# 4_motor.net
KiCad netlist of a schematic drawn in Altium Designer
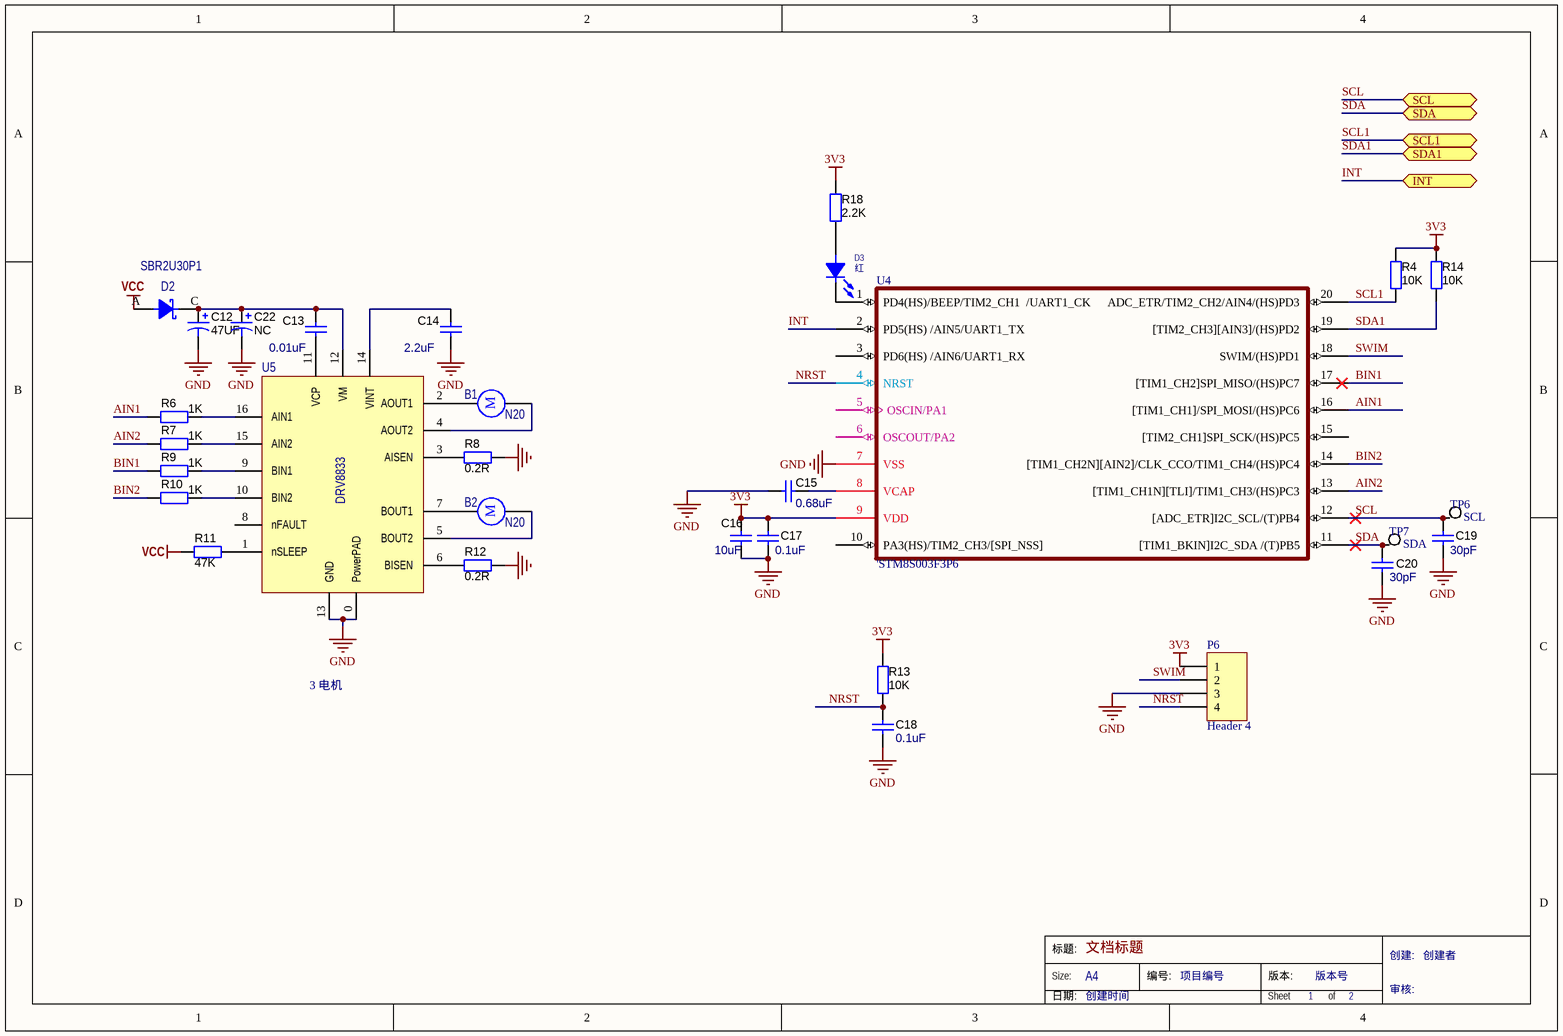
[diagram p0: 4.motor.SchDoc]

(export (version "E")
  (design (tool "Eeschema 10.0.6"))
  (components
    (comp (ref "B1")
      (value "N20")
      (footprint "2PIN/2.54MM座子")
      (description "Motor, General Kind")
      (fields (field (name "PUBLISHER") "Altium Limited"))
      (libsource (lib "Miscellaneous Devices") (part "Motor"))
    )
    (comp (ref "B2")
      (value "N20")
      (footprint "2PIN/2.54MM座子")
      (description "Motor, General Kind")
      (fields (field (name "PUBLISHER") "Altium Limited"))
      (libsource (lib "Miscellaneous Devices") (part "Motor"))
    )
    (comp (ref "C12")
      (value "47UF")
      (footprint "1206")
      (description "CAP ALUM 22UF 10V 20% SMD")
      (fields
        (field (name "PARTNUMBER") "EEE-1AA220WR")
        (field (name "MANUFACTURER") "Panasonic - ECG")
        (field (name "PUBLISHER") "National Semiconductor")
      )
      (libsource (lib "03.常用器件") (part "CAP3_pol"))
    )
    (comp (ref "C13")
      (value "0.01uF")
      (footprint "0402")
      (description "CAP, CERM, 0.01uF, 100V, +/-5%, X7R, 0603")
      (fields (field (name "PARTNUMBER") "06031C103JAT2A") (field (name "MANUFACTURER") "AVX"))
      (libsource (lib "03.常用器件") (part "CAP1_npol"))
    )
    (comp (ref "C14")
      (value "2.2uF")
      (footprint "0402")
      (description "CAP, CERM, 0.01uF, 100V, +/-5%, X7R, 0603")
      (fields (field (name "PARTNUMBER") "06031C103JAT2A") (field (name "MANUFACTURER") "AVX"))
      (libsource (lib "03.常用器件") (part "CAP1_npol"))
    )
    (comp (ref "C15")
      (value "0.68uF")
      (footprint "0402")
      (description "CAP, CERM, 0.01uF, 100V, +/-5%, X7R, 0603")
      (fields (field (name "PARTNUMBER") "06031C103JAT2A") (field (name "MANUFACTURER") "AVX"))
      (libsource (lib "03.常用器件") (part "CAP1_npol"))
    )
    (comp (ref "C16")
      (value "10uF")
      (footprint "0603")
      (description "CAP, CERM, 0.01uF, 100V, +/-5%, X7R, 0603")
      (fields (field (name "PARTNUMBER") "06031C103JAT2A") (field (name "MANUFACTURER") "AVX"))
      (libsource (lib "03.常用器件") (part "CAP1_npol"))
    )
    (comp (ref "C17")
      (value "0.1uF")
      (footprint "0402")
      (description "CAP, CERM, 0.01uF, 100V, +/-5%, X7R, 0603")
      (fields (field (name "PARTNUMBER") "06031C103JAT2A") (field (name "MANUFACTURER") "AVX"))
      (libsource (lib "03.常用器件") (part "CAP1_npol"))
    )
    (comp (ref "C18")
      (value "0.1uF")
      (footprint "0402")
      (description "CAP, CERM, 0.01uF, 100V, +/-5%, X7R, 0603")
      (fields (field (name "PARTNUMBER") "06031C103JAT2A") (field (name "MANUFACTURER") "AVX"))
      (libsource (lib "03.常用器件") (part "CAP1_npol"))
    )
    (comp (ref "C19")
      (value "30pF")
      (footprint "0402")
      (description "CAP, CERM, 0.01uF, 100V, +/-5%, X7R, 0603")
      (fields (field (name "PARTNUMBER") "06031C103JAT2A") (field (name "MANUFACTURER") "AVX"))
      (libsource (lib "03.常用器件") (part "CAP1_npol"))
    )
    (comp (ref "C20")
      (value "30pF")
      (footprint "0402")
      (description "CAP, CERM, 0.01uF, 100V, +/-5%, X7R, 0603")
      (fields (field (name "PARTNUMBER") "06031C103JAT2A") (field (name "MANUFACTURER") "AVX"))
      (libsource (lib "03.常用器件") (part "CAP1_npol"))
    )
    (comp (ref "C22")
      (value "NC")
      (footprint "1206")
      (description "CAP ALUM 22UF 10V 20% SMD")
      (fields
        (field (name "PARTNUMBER") "EEE-1AA220WR")
        (field (name "MANUFACTURER") "Panasonic - ECG")
        (field (name "PUBLISHER") "National Semiconductor")
      )
      (libsource (lib "03.常用器件") (part "CAP3_pol"))
    )
    (comp (ref "D2")
      (value "SBR2U30P1")
      (footprint "POWERDI123")
      (fields (field (name "PARTNUMBER") "?") (field (name "PUBLISHER") "Altium Limited"))
      (libsource (lib "03.常用器件") (part "Diode_Schottky"))
    )
    (comp (ref "D3")
      (value "红")
      (footprint "0603LED")
      (fields (field (name "MANUFACTURER") "?"))
      (libsource (lib "03.常用器件") (part "LED1"))
    )
    (comp (ref "P6")
      (value "Header 4")
      (footprint "排针2.54MM/4PIN")
      (description "Header, 4-Pin")
      (fields (field (name "PUBLISHER") "Altium Limited"))
      (libsource (lib "Miscellaneous Connectors") (part "Header 4"))
    )
    (comp (ref "R4")
      (value "10K")
      (footprint "0402")
      (description "RES, 1.0k ohm, 5%, 0.1W, 0603")
      (fields
        (field (name "PARTNUMBER") "RC0603JR-071KL")
        (field (name "MANUFACTURER") "Yageo America")
        (field (name "PUBLISHER") "Texas Instruments")
      )
      (libsource (lib "03.常用器件") (part "RES1"))
    )
    (comp (ref "R6")
      (value "1K")
      (footprint "0402")
      (description "RES, 1.0k ohm, 5%, 0.1W, 0603")
      (fields
        (field (name "PARTNUMBER") "RC0603JR-071KL")
        (field (name "MANUFACTURER") "Yageo America")
        (field (name "PUBLISHER") "Texas Instruments")
      )
      (libsource (lib "") (part "RES1_1"))
    )
    (comp (ref "R7")
      (value "1K")
      (footprint "0402")
      (description "RES, 1.0k ohm, 5%, 0.1W, 0603")
      (fields
        (field (name "PARTNUMBER") "RC0603JR-071KL")
        (field (name "MANUFACTURER") "Yageo America")
        (field (name "PUBLISHER") "Texas Instruments")
      )
      (libsource (lib "") (part "RES1_1"))
    )
    (comp (ref "R8")
      (value "0.2R")
      (footprint "0603")
      (description "RES, 1.0k ohm, 5%, 0.1W, 0603")
      (fields
        (field (name "PARTNUMBER") "RC0603JR-071KL")
        (field (name "MANUFACTURER") "Yageo America")
        (field (name "PUBLISHER") "Texas Instruments")
      )
      (libsource (lib "") (part "RES1_1"))
    )
    (comp (ref "R9")
      (value "1K")
      (footprint "0402")
      (description "RES, 1.0k ohm, 5%, 0.1W, 0603")
      (fields
        (field (name "PARTNUMBER") "RC0603JR-071KL")
        (field (name "MANUFACTURER") "Yageo America")
        (field (name "PUBLISHER") "Texas Instruments")
      )
      (libsource (lib "") (part "RES1_1"))
    )
    (comp (ref "R10")
      (value "1K")
      (footprint "0402")
      (description "RES, 1.0k ohm, 5%, 0.1W, 0603")
      (fields
        (field (name "PARTNUMBER") "RC0603JR-071KL")
        (field (name "MANUFACTURER") "Yageo America")
        (field (name "PUBLISHER") "Texas Instruments")
      )
      (libsource (lib "") (part "RES1_1"))
    )
    (comp (ref "R11")
      (value "47K")
      (footprint "0402")
      (description "RES, 1.0k ohm, 5%, 0.1W, 0603")
      (fields
        (field (name "PARTNUMBER") "RC0603JR-071KL")
        (field (name "MANUFACTURER") "Yageo America")
        (field (name "PUBLISHER") "Texas Instruments")
      )
      (libsource (lib "") (part "RES1_1"))
    )
    (comp (ref "R12")
      (value "0.2R")
      (footprint "0603")
      (description "RES, 1.0k ohm, 5%, 0.1W, 0603")
      (fields
        (field (name "PARTNUMBER") "RC0603JR-071KL")
        (field (name "MANUFACTURER") "Yageo America")
        (field (name "PUBLISHER") "Texas Instruments")
      )
      (libsource (lib "") (part "RES1_1"))
    )
    (comp (ref "R13")
      (value "10K")
      (footprint "0402")
      (description "RES, 1.0k ohm, 5%, 0.1W, 0603")
      (fields
        (field (name "PARTNUMBER") "RC0603JR-071KL")
        (field (name "MANUFACTURER") "Yageo America")
        (field (name "PUBLISHER") "Texas Instruments")
      )
      (libsource (lib "") (part "RES1_2"))
    )
    (comp (ref "R14")
      (value "10K")
      (footprint "0402")
      (description "RES, 1.0k ohm, 5%, 0.1W, 0603")
      (fields
        (field (name "PARTNUMBER") "RC0603JR-071KL")
        (field (name "MANUFACTURER") "Yageo America")
        (field (name "PUBLISHER") "Texas Instruments")
      )
      (libsource (lib "03.常用器件") (part "RES1"))
    )
    (comp (ref "R18")
      (value "2.2K")
      (footprint "0402")
      (description "RES, 1.0k ohm, 5%, 0.1W, 0603")
      (fields
        (field (name "PARTNUMBER") "RC0603JR-071KL")
        (field (name "MANUFACTURER") "Yageo America")
        (field (name "PUBLISHER") "Texas Instruments")
      )
      (libsource (lib "") (part "RES1_2"))
    )
    (comp (ref "TP6")
      (value "SCL")
      (footprint "测试点")
      (description "Test Point")
      (libsource (lib "my_Schlib") (part "TP"))
    )
    (comp (ref "TP7")
      (value "SDA")
      (footprint "测试点")
      (description "Test Point")
      (libsource (lib "my_Schlib") (part "TP"))
    )
    (comp (ref "U4")
      (value "'STM8S003F3P6")
      (footprint "UFQFPN20")
      (description "ST 8-bit  Microcontroller")
      (libsource (lib "Microcontroller Unit") (part "STM8S103F2P6"))
    )
    (comp (ref "U5")
      (value "DRV8833")
      (footprint "HTSSOP -16(PWP)")
      (description "DUAL H-BRIDGE MOTOR DRIVER")
      (libsource (lib "DRV8833") (part "DRV8833PWP"))
    )
  )
  (nets
    (net (code "1") (name "/AIN1") (class "Default")
      (node (ref "R6") (pin "1") (pinfunction "1_1") (pintype "passive"))
      (node (ref "U4") (pin "16") (pinfunction "[TIM1_CH1]/SPI_MOSI/(HS)PC6_16") (pintype "bidirectional"))
    )
    (net (code "2") (name "/AIN2") (class "Default")
      (node (ref "R7") (pin "1") (pinfunction "1_1") (pintype "passive"))
      (node (ref "U4") (pin "13") (pinfunction "[TIM1_CH1N][TLI]/TIM1_CH3/(HS)PC3_13") (pintype "bidirectional"))
    )
    (net (code "3") (name "/BIN1") (class "Default")
      (node (ref "R9") (pin "1") (pinfunction "1_1") (pintype "passive"))
      (node (ref "U4") (pin "17") (pinfunction "[TIM1_CH2]SPI_MISO/(HS)PC7_17") (pintype "bidirectional"))
    )
    (net (code "4") (name "/BIN2") (class "Default")
      (node (ref "R10") (pin "1") (pinfunction "1_1") (pintype "passive"))
      (node (ref "U4") (pin "14") (pinfunction "[TIM1_CH2N][AIN2]/CLK_CCO/TIM1_CH4/(HS)PC4_14") (pintype "bidirectional"))
    )
    (net (code "5") (name "/INT") (class "Default")
      (node (ref "U4") (pin "2") (pinfunction "PD5(HS)_/AIN5/UART1_TX_2") (pintype "bidirectional"))
    )
    (net (code "6") (name "/NRST") (class "Default")
      (node (ref "C18") (pin "2") (pinfunction "2_2") (pintype "passive"))
      (node (ref "P6") (pin "4") (pinfunction "4_4") (pintype "passive"))
      (node (ref "R13") (pin "2") (pinfunction "2_2") (pintype "passive"))
      (node (ref "U4") (pin "4") (pinfunction "NRST_4") (pintype "bidirectional"))
    )
    (net (code "8") (name "/SCL") (class "Default")
      (node (ref "C19") (pin "2") (pinfunction "2_2") (pintype "passive"))
      (node (ref "TP6") (pin "1") (pinfunction "1_1") (pintype "passive"))
      (node (ref "U4") (pin "12") (pinfunction "[ADC_ETR]I2C_SCL/(T)PB4_12") (pintype "bidirectional"))
    )
    (net (code "10") (name "/SCL1") (class "Default")
      (node (ref "R4") (pin "1") (pinfunction "1_1") (pintype "passive"))
      (node (ref "U4") (pin "20") (pinfunction "ADC_ETR/TIM2_CH2/AIN4/(HS)PD3_20") (pintype "bidirectional"))
    )
    (net (code "11") (name "/SDA") (class "Default")
      (node (ref "C20") (pin "2") (pinfunction "2_2") (pintype "passive"))
      (node (ref "TP7") (pin "1") (pinfunction "1_1") (pintype "passive"))
      (node (ref "U4") (pin "11") (pinfunction "[TIM1_BKIN]I2C_SDA_/(T)PB5_11") (pintype "bidirectional"))
    )
    (net (code "12") (name "/SDA1") (class "Default")
      (node (ref "R14") (pin "1") (pinfunction "1_1") (pintype "passive"))
      (node (ref "U4") (pin "19") (pinfunction "[TIM2_CH3][AIN3]/(HS)PD2_19") (pintype "bidirectional"))
    )
    (net (code "13") (name "/SWIM") (class "Default")
      (node (ref "P6") (pin "2") (pinfunction "2_2") (pintype "passive"))
      (node (ref "U4") (pin "18") (pinfunction "SWIM/(HS)PD1_18") (pintype "bidirectional"))
    )
    (net (code "14") (name "3V3") (class "Default")
      (node (ref "C16") (pin "1") (pinfunction "1_1") (pintype "passive"))
      (node (ref "C17") (pin "2") (pinfunction "2_2") (pintype "passive"))
      (node (ref "P6") (pin "1") (pinfunction "1_1") (pintype "passive"))
      (node (ref "R13") (pin "1") (pinfunction "1_1") (pintype "passive"))
      (node (ref "R14") (pin "2") (pinfunction "2_2") (pintype "passive"))
      (node (ref "R18") (pin "1") (pinfunction "1_1") (pintype "passive"))
      (node (ref "R4") (pin "2") (pinfunction "2_2") (pintype "passive"))
      (node (ref "U4") (pin "9") (pinfunction "VDD_9") (pintype "power_in"))
    )
    (net (code "15") (name "GND") (class "Default")
      (node (ref "C12") (pin "2") (pinfunction "-_2") (pintype "passive"))
      (node (ref "C14") (pin "1") (pinfunction "1_1") (pintype "passive"))
      (node (ref "C15") (pin "2") (pinfunction "2_2") (pintype "passive"))
      (node (ref "C16") (pin "2") (pinfunction "2_2") (pintype "passive"))
      (node (ref "C17") (pin "1") (pinfunction "1_1") (pintype "passive"))
      (node (ref "C18") (pin "1") (pinfunction "1_1") (pintype "passive"))
      (node (ref "C19") (pin "1") (pinfunction "1_1") (pintype "passive"))
      (node (ref "C20") (pin "1") (pinfunction "1_1") (pintype "passive"))
      (node (ref "C22") (pin "2") (pinfunction "-_2") (pintype "passive"))
      (node (ref "P6") (pin "3") (pinfunction "3_3") (pintype "passive"))
      (node (ref "R12") (pin "2") (pinfunction "2_2") (pintype "passive"))
      (node (ref "R8") (pin "2") (pinfunction "2_2") (pintype "passive"))
      (node (ref "U4") (pin "7") (pinfunction "VSS_7") (pintype "power_in"))
      (node (ref "U5") (pin "0") (pinfunction "PowerPAD_0") (pintype "passive"))
      (node (ref "U5") (pin "13") (pinfunction "GND_13") (pintype "passive"))
    )
    (net (code "16") (name "Net-(C12-+)") (class "Default")
      (node (ref "C12") (pin "1") (pinfunction "+_1") (pintype "passive"))
      (node (ref "C13") (pin "2") (pinfunction "2_2") (pintype "passive"))
      (node (ref "C22") (pin "1") (pinfunction "+_1") (pintype "passive"))
      (node (ref "D2") (pin "C") (pinfunction "CATHODE_C") (pintype "passive"))
      (node (ref "U5") (pin "12") (pinfunction "VM_12") (pintype "passive"))
    )
    (net (code "17") (name "Net-(D3-ANODE)") (class "Default")
      (node (ref "D3") (pin "A") (pinfunction "ANODE_A") (pintype "passive"))
      (node (ref "R18") (pin "2") (pinfunction "2_2") (pintype "passive"))
    )
    (net (code "18") (name "Net-(D3-CATHODE)") (class "Default")
      (node (ref "D3") (pin "C") (pinfunction "CATHODE_C") (pintype "passive"))
      (node (ref "U4") (pin "1") (pinfunction "PD4(HS)/BEEP/TIM2_CH1__/UART1_CK_1") (pintype "bidirectional"))
    )
    (net (code "19") (name "Net-(U4-VCAP)") (class "Default")
      (node (ref "C15") (pin "1") (pinfunction "1_1") (pintype "passive"))
      (node (ref "U4") (pin "8") (pinfunction "VCAP_8") (pintype "power_in"))
    )
    (net (code "20") (name "Net-(U5-AIN1)") (class "Default")
      (node (ref "R6") (pin "2") (pinfunction "2_2") (pintype "passive"))
      (node (ref "U5") (pin "16") (pinfunction "AIN1_16") (pintype "passive"))
    )
    (net (code "21") (name "Net-(U5-AIN2)") (class "Default")
      (node (ref "R7") (pin "2") (pinfunction "2_2") (pintype "passive"))
      (node (ref "U5") (pin "15") (pinfunction "AIN2_15") (pintype "passive"))
    )
    (net (code "22") (name "Net-(U5-AISEN)") (class "Default")
      (node (ref "R8") (pin "1") (pinfunction "1_1") (pintype "passive"))
      (node (ref "U5") (pin "3") (pinfunction "AISEN_3") (pintype "passive"))
    )
    (net (code "23") (name "Net-(U5-AOUT1)") (class "Default")
      (node (ref "B1") (pin "1") (pinfunction "1_1") (pintype "passive"))
      (node (ref "U5") (pin "2") (pinfunction "AOUT1_2") (pintype "passive"))
    )
    (net (code "24") (name "Net-(U5-AOUT2)") (class "Default")
      (node (ref "B1") (pin "2") (pinfunction "2_2") (pintype "passive"))
      (node (ref "U5") (pin "4") (pinfunction "AOUT2_4") (pintype "passive"))
    )
    (net (code "25") (name "Net-(U5-BIN1)") (class "Default")
      (node (ref "R9") (pin "2") (pinfunction "2_2") (pintype "passive"))
      (node (ref "U5") (pin "9") (pinfunction "BIN1_9") (pintype "passive"))
    )
    (net (code "26") (name "Net-(U5-BIN2)") (class "Default")
      (node (ref "R10") (pin "2") (pinfunction "2_2") (pintype "passive"))
      (node (ref "U5") (pin "10") (pinfunction "BIN2_10") (pintype "passive"))
    )
    (net (code "27") (name "Net-(U5-BISEN)") (class "Default")
      (node (ref "R12") (pin "1") (pinfunction "1_1") (pintype "passive"))
      (node (ref "U5") (pin "6") (pinfunction "BISEN_6") (pintype "passive"))
    )
    (net (code "28") (name "Net-(U5-BOUT1)") (class "Default")
      (node (ref "B2") (pin "1") (pinfunction "1_1") (pintype "passive"))
      (node (ref "U5") (pin "7") (pinfunction "BOUT1_7") (pintype "passive"))
    )
    (net (code "29") (name "Net-(U5-BOUT2)") (class "Default")
      (node (ref "B2") (pin "2") (pinfunction "2_2") (pintype "passive"))
      (node (ref "U5") (pin "5") (pinfunction "BOUT2_5") (pintype "passive"))
    )
    (net (code "30") (name "Net-(U5-VCP)") (class "Default")
      (node (ref "C13") (pin "1") (pinfunction "1_1") (pintype "passive"))
      (node (ref "U5") (pin "11") (pinfunction "VCP_11") (pintype "passive"))
    )
    (net (code "31") (name "Net-(U5-VINT)") (class "Default")
      (node (ref "C14") (pin "2") (pinfunction "2_2") (pintype "passive"))
      (node (ref "U5") (pin "14") (pinfunction "VINT_14") (pintype "passive"))
    )
    (net (code "32") (name "Net-(U5-nSLEEP)") (class "Default")
      (node (ref "R11") (pin "2") (pinfunction "2_2") (pintype "passive"))
      (node (ref "U5") (pin "1") (pinfunction "nSLEEP_1") (pintype "passive"))
    )
    (net (code "33") (name "VCC") (class "Default")
      (node (ref "D2") (pin "A") (pinfunction "ANODE_A") (pintype "passive"))
      (node (ref "R11") (pin "1") (pinfunction "1_1") (pintype "passive"))
    )
    (net (code "34") (name "unconnected-(U4-OSCIN{slash}PA1-Pad5)") (class "Default")
      (node (ref "U4") (pin "5") (pinfunction "OSCIN/PA1_5") (pintype "bidirectional"))
    )
    (net (code "35") (name "unconnected-(U4-OSCOUT{slash}PA2-Pad6)") (class "Default")
      (node (ref "U4") (pin "6") (pinfunction "OSCOUT/PA2_6") (pintype "bidirectional"))
    )
    (net (code "36") (name "unconnected-(U4-PA3(HS){slash}TIM2_CH3{slash}[SPI_NSS]-Pad10)") (class "Default")
      (node (ref "U4") (pin "10") (pinfunction "PA3(HS)/TIM2_CH3/[SPI_NSS]_10") (pintype "bidirectional"))
    )
    (net (code "37") (name "unconnected-(U4-PD6(HS)_{slash}AIN6{slash}UART1_RX-Pad3)") (class "Default")
      (node (ref "U4") (pin "3") (pinfunction "PD6(HS)_/AIN6/UART1_RX_3") (pintype "bidirectional"))
    )
    (net (code "38") (name "unconnected-(U4-[TIM2_CH1]SPI_SCK{slash}(HS)PC5-Pad15)") (class "Default")
      (node (ref "U4") (pin "15") (pinfunction "[TIM2_CH1]SPI_SCK/(HS)PC5_15") (pintype "bidirectional"))
    )
    (net (code "39") (name "unconnected-(U5-nFAULT-Pad8)") (class "Default")
      (node (ref "U5") (pin "8") (pinfunction "nFAULT_8") (pintype "passive"))
    )
  )
)
